# d_enc_v3.net
KiCad netlist of a schematic drawn in EAGLE
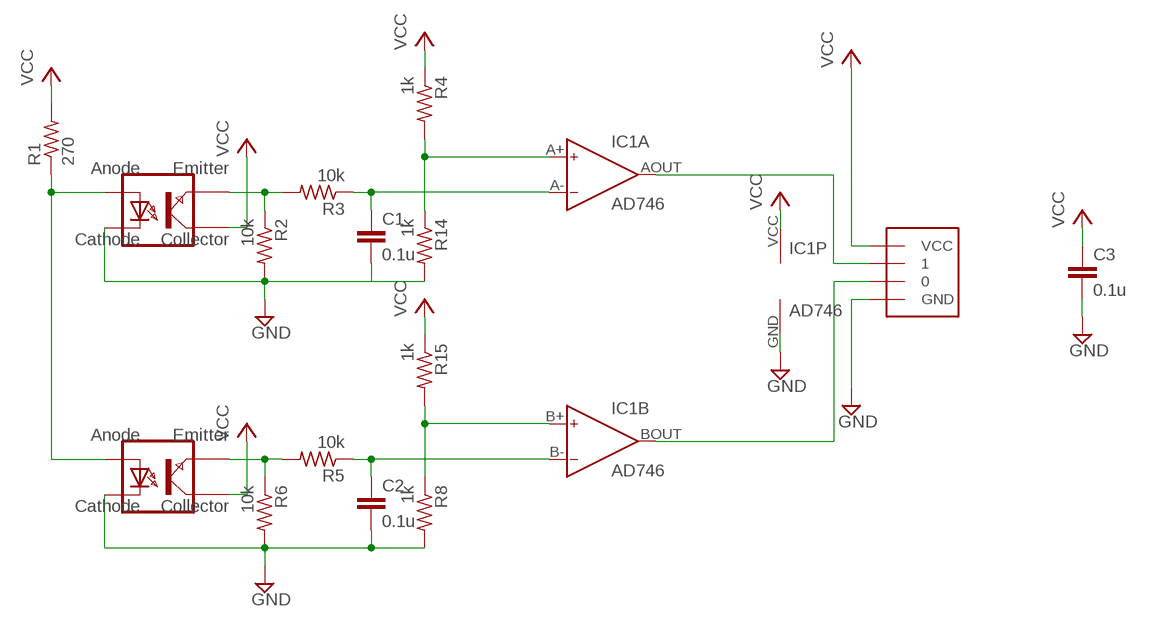
[diagram p0: schematic, sheet 1]

(export (version "E")
  (design (tool "Eeschema 10.0.6"))
  (components
    (comp (ref "C1")
      (value "0.1u")
      (footprint "eagle-import:C0603")
      (libsource (lib "eagle-import") (part "C-EUC0603"))
    )
    (comp (ref "C2")
      (value "0.1u")
      (footprint "eagle-import:C0603")
      (libsource (lib "eagle-import") (part "C-EUC0603"))
    )
    (comp (ref "C3")
      (value "0.1u")
      (footprint "eagle-import:C0603")
      (libsource (lib "eagle-import") (part "C-EUC0603"))
    )
    (comp (ref "IC1")
      (value "AD746")
      (footprint "eagle-import:NJM2903E")
      (libsource (lib "eagle-import") (part "AD746"))
    )
    (comp (ref "R1")
      (value "270")
      (footprint "eagle-import:R0603")
      (libsource (lib "eagle-import") (part "R-US_R0603"))
    )
    (comp (ref "R2")
      (value "10k")
      (footprint "eagle-import:R0603")
      (libsource (lib "eagle-import") (part "R-US_R0603"))
    )
    (comp (ref "R3")
      (value "10k")
      (footprint "eagle-import:R0603")
      (libsource (lib "eagle-import") (part "R-US_R0603"))
    )
    (comp (ref "R4")
      (value "1k")
      (footprint "eagle-import:R0603")
      (libsource (lib "eagle-import") (part "R-US_R0603"))
    )
    (comp (ref "R5")
      (value "10k")
      (footprint "eagle-import:R0603")
      (libsource (lib "eagle-import") (part "R-US_R0603"))
    )
    (comp (ref "R6")
      (value "10k")
      (footprint "eagle-import:R0603")
      (libsource (lib "eagle-import") (part "R-US_R0603"))
    )
    (comp (ref "R8")
      (value "1k")
      (footprint "eagle-import:R0603")
      (libsource (lib "eagle-import") (part "R-US_R0603"))
    )
    (comp (ref "R14")
      (value "1k")
      (footprint "eagle-import:R0603")
      (libsource (lib "eagle-import") (part "R-US_R0603"))
    )
    (comp (ref "R15")
      (value "1k")
      (footprint "eagle-import:R0603")
      (libsource (lib "eagle-import") (part "R-US_R0603"))
    )
    (comp (ref "U$1")
      (value "TPR-105F")
      (footprint "eagle-import:TPR-105F")
      (libsource (lib "eagle-import") (part "TPR-105F"))
    )
    (comp (ref "U$2")
      (value "ENC_CON")
      (footprint "eagle-import:ENC_CON")
      (libsource (lib "eagle-import") (part "ENC_CON"))
    )
    (comp (ref "U$4")
      (value "TPR-105F")
      (footprint "eagle-import:TPR-105F")
      (libsource (lib "eagle-import") (part "TPR-105F"))
    )
  )
  (nets
    (net (code "1") (name "GND") (class "Default")
      (node (ref "C1") (pin "2") (pinfunction "2_2") (pintype "passive"))
      (node (ref "C2") (pin "2") (pinfunction "2_2") (pintype "passive"))
      (node (ref "C3") (pin "2") (pinfunction "2_2") (pintype "passive"))
      (node (ref "IC1") (pin "GND") (pinfunction "V-_GND") (pintype "power_in"))
      (node (ref "R14") (pin "2") (pinfunction "2_2") (pintype "passive"))
      (node (ref "R2") (pin "2") (pinfunction "2_2") (pintype "passive"))
      (node (ref "R6") (pin "2") (pinfunction "2_2") (pintype "passive"))
      (node (ref "R8") (pin "2") (pinfunction "2_2") (pintype "passive"))
      (node (ref "U$1") (pin "CATHODE") (pinfunction "CATHODE_CATHODE") (pintype "bidirectional"))
      (node (ref "U$2") (pin "GND") (pinfunction "GND_GND") (pintype "bidirectional"))
      (node (ref "U$4") (pin "CATHODE") (pinfunction "CATHODE_CATHODE") (pintype "bidirectional"))
    )
    (net (code "2") (name "Net-(IC1A-IN+)") (class "Default")
      (node (ref "IC1") (pin "A+") (pinfunction "IN+_A+") (pintype "input"))
      (node (ref "R14") (pin "1") (pinfunction "1_1") (pintype "passive"))
      (node (ref "R4") (pin "2") (pinfunction "2_2") (pintype "passive"))
    )
    (net (code "3") (name "Net-(IC1A-IN-)") (class "Default")
      (node (ref "C1") (pin "1") (pinfunction "1_1") (pintype "passive"))
      (node (ref "IC1") (pin "A-") (pinfunction "IN-_A-") (pintype "input"))
      (node (ref "R3") (pin "1") (pinfunction "1_1") (pintype "passive"))
    )
    (net (code "4") (name "Net-(IC1A-OUT)") (class "Default")
      (node (ref "IC1") (pin "AOUT") (pinfunction "OUT_AOUT") (pintype "output"))
      (node (ref "U$2") (pin "1") (pinfunction "1_1") (pintype "bidirectional"))
    )
    (net (code "5") (name "Net-(IC1B-IN+)") (class "Default")
      (node (ref "IC1") (pin "B+") (pinfunction "IN+_B+") (pintype "input"))
      (node (ref "R15") (pin "2") (pinfunction "2_2") (pintype "passive"))
      (node (ref "R8") (pin "1") (pinfunction "1_1") (pintype "passive"))
    )
    (net (code "6") (name "Net-(IC1B-IN-)") (class "Default")
      (node (ref "C2") (pin "1") (pinfunction "1_1") (pintype "passive"))
      (node (ref "IC1") (pin "B-") (pinfunction "IN-_B-") (pintype "input"))
      (node (ref "R5") (pin "1") (pinfunction "1_1") (pintype "passive"))
    )
    (net (code "7") (name "Net-(IC1B-OUT)") (class "Default")
      (node (ref "IC1") (pin "BOUT") (pinfunction "OUT_BOUT") (pintype "output"))
      (node (ref "U$2") (pin "0") (pinfunction "0_0") (pintype "bidirectional"))
    )
    (net (code "8") (name "Net-(R1-Pad1)") (class "Default")
      (node (ref "R1") (pin "1") (pinfunction "1_1") (pintype "passive"))
      (node (ref "U$1") (pin "ANODE") (pinfunction "ANODE_ANODE") (pintype "bidirectional"))
      (node (ref "U$4") (pin "ANODE") (pinfunction "ANODE_ANODE") (pintype "bidirectional"))
    )
    (net (code "9") (name "Net-(R2-Pad1)") (class "Default")
      (node (ref "R2") (pin "1") (pinfunction "1_1") (pintype "passive"))
      (node (ref "R3") (pin "2") (pinfunction "2_2") (pintype "passive"))
      (node (ref "U$4") (pin "EMITTER") (pinfunction "EMITTER_EMITTER") (pintype "bidirectional"))
    )
    (net (code "10") (name "Net-(R5-Pad2)") (class "Default")
      (node (ref "R5") (pin "2") (pinfunction "2_2") (pintype "passive"))
      (node (ref "R6") (pin "1") (pinfunction "1_1") (pintype "passive"))
      (node (ref "U$1") (pin "EMITTER") (pinfunction "EMITTER_EMITTER") (pintype "bidirectional"))
    )
    (net (code "11") (name "VCC") (class "Default")
      (node (ref "C3") (pin "1") (pinfunction "1_1") (pintype "passive"))
      (node (ref "IC1") (pin "VCC") (pinfunction "V+_VCC") (pintype "power_in"))
      (node (ref "R1") (pin "2") (pinfunction "2_2") (pintype "passive"))
      (node (ref "R15") (pin "1") (pinfunction "1_1") (pintype "passive"))
      (node (ref "R4") (pin "1") (pinfunction "1_1") (pintype "passive"))
      (node (ref "U$1") (pin "COLLECTOR") (pinfunction "COLLECTOR_COLLECTOR") (pintype "bidirectional"))
      (node (ref "U$2") (pin "VCC") (pinfunction "VCC_VCC") (pintype "bidirectional"))
      (node (ref "U$4") (pin "COLLECTOR") (pinfunction "COLLECTOR_COLLECTOR") (pintype "bidirectional"))
    )
  )
)
